# fuzz_sch.net
KiCad netlist of a schematic drawn in EAGLE
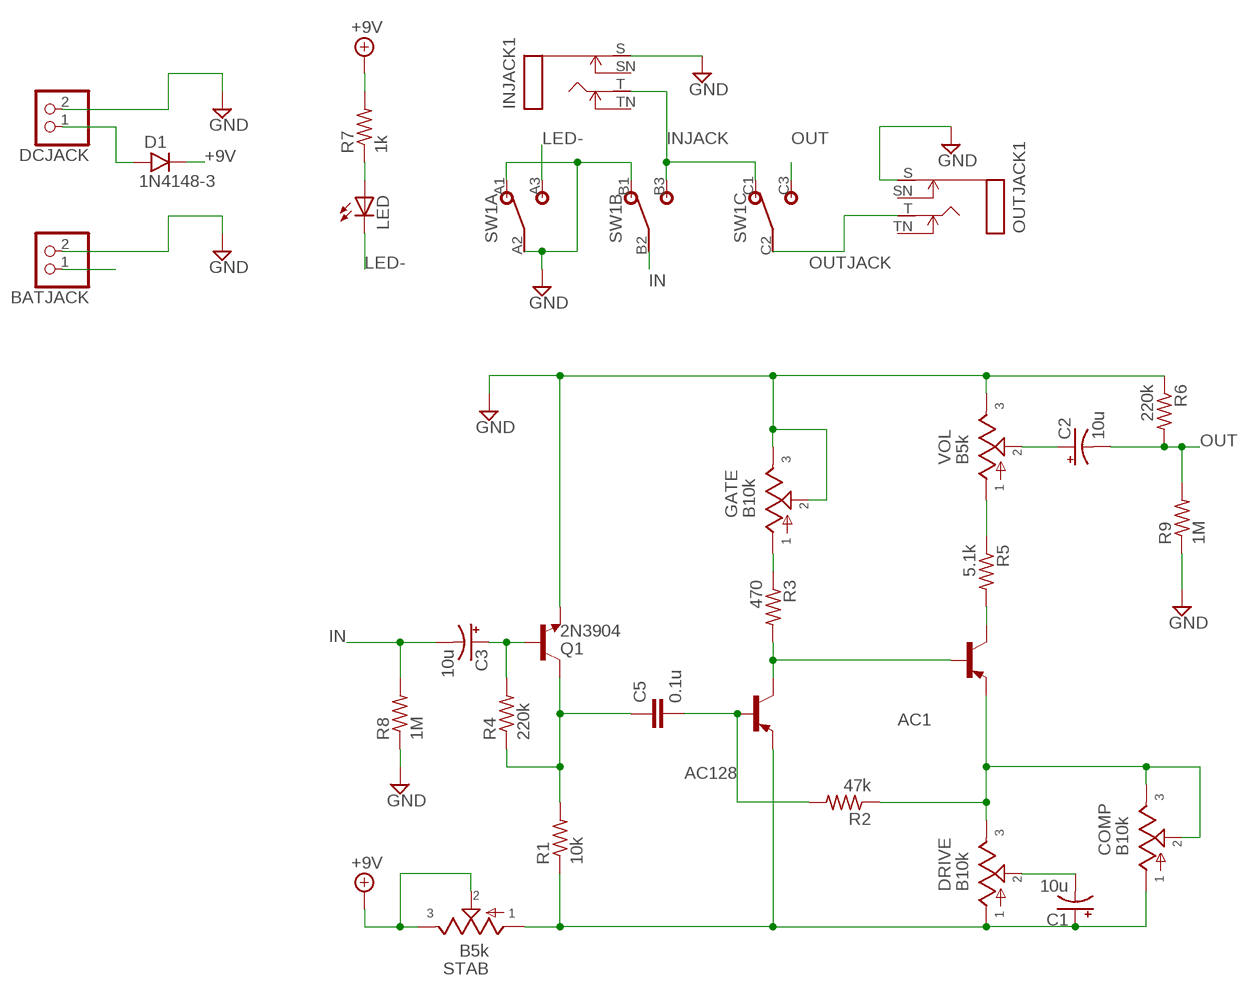
[diagram p0: schematic, sheet 1]

(export (version "E")
  (design (tool "Eeschema 10.0.6"))
  (components
    (comp (ref "AC1")
      (value "-PNP-TO5")
      (footprint "eagle-import:TO5")
      (libsource (lib "eagle-import") (part "-PNP-TO5"))
    )
    (comp (ref "AC128")
      (value "-PNP-TO5")
      (footprint "eagle-import:TO5")
      (libsource (lib "eagle-import") (part "-PNP-TO5"))
    )
    (comp (ref "BATJACK")
      (value "PINHD-1X2")
      (footprint "eagle-import:1X02")
      (libsource (lib "eagle-import") (part "PINHD-1X2"))
    )
    (comp (ref "C1")
      (value "10u")
      (footprint "eagle-import:063_025")
      (libsource (lib "eagle-import") (part "0631"))
    )
    (comp (ref "C2")
      (value "10u")
      (footprint "eagle-import:063_025")
      (libsource (lib "eagle-import") (part "0631"))
    )
    (comp (ref "C3")
      (value "10u")
      (footprint "eagle-import:063_025")
      (libsource (lib "eagle-import") (part "0631"))
    )
    (comp (ref "C5")
      (value "0.1u")
      (footprint "eagle-import:072X035")
      (libsource (lib "eagle-import") (part "072X0352"))
    )
    (comp (ref "COMP")
      (value "B10k")
      (footprint "eagle-import:16MM")
      (libsource (lib "eagle-import") (part "POT16MM"))
    )
    (comp (ref "D1")
      (value "1N4148-3")
      (footprint "eagle-import:DO35-3")
      (libsource (lib "eagle-import") (part "1N4148-3"))
    )
    (comp (ref "DCJACK")
      (value "PINHD-1X2")
      (footprint "eagle-import:1X02")
      (libsource (lib "eagle-import") (part "PINHD-1X2"))
    )
    (comp (ref "DRIVE")
      (value "B10k")
      (footprint "eagle-import:16MM")
      (libsource (lib "eagle-import") (part "POT16MM"))
    )
    (comp (ref "GATE")
      (value "B10k")
      (footprint "eagle-import:16MM")
      (libsource (lib "eagle-import") (part "POT16MM"))
    )
    (comp (ref "INJACK1")
      (value "MONOSWS")
      (footprint "eagle-import:NMJ4HC-S")
      (libsource (lib "eagle-import") (part "MONOSWS"))
    )
    (comp (ref "LED")
      (value "LED5MM")
      (footprint "eagle-import:LED5MM")
      (libsource (lib "eagle-import") (part "LED5MM"))
    )
    (comp (ref "OUTJACK1")
      (value "MONOSWS")
      (footprint "eagle-import:NMJ4HC-S")
      (libsource (lib "eagle-import") (part "MONOSWS"))
    )
    (comp (ref "Q1")
      (value "2N3904")
      (footprint "eagle-import:TO92-")
      (libsource (lib "eagle-import") (part "2N3904"))
    )
    (comp (ref "R1")
      (value "10k")
      (footprint "eagle-import:0207_10")
      (libsource (lib "eagle-import") (part "R-US_0207/10"))
    )
    (comp (ref "R2")
      (value "47k")
      (footprint "eagle-import:0207_10")
      (libsource (lib "eagle-import") (part "R-US_0207/10"))
    )
    (comp (ref "R3")
      (value "470")
      (footprint "eagle-import:0207_10")
      (libsource (lib "eagle-import") (part "R-US_0207/10"))
    )
    (comp (ref "R4")
      (value "220k")
      (footprint "eagle-import:0207_10")
      (libsource (lib "eagle-import") (part "R-US_0207/10"))
    )
    (comp (ref "R5")
      (value "5.1k")
      (footprint "eagle-import:0207_10")
      (libsource (lib "eagle-import") (part "R-US_0207/10"))
    )
    (comp (ref "R6")
      (value "220k")
      (footprint "eagle-import:0207_10")
      (libsource (lib "eagle-import") (part "R-US_0207/10"))
    )
    (comp (ref "R7")
      (value "1k")
      (footprint "eagle-import:0207_10")
      (libsource (lib "eagle-import") (part "R-US_0207/10"))
    )
    (comp (ref "R8")
      (value "1M")
      (footprint "eagle-import:0207_10")
      (libsource (lib "eagle-import") (part "R-US_0207/10"))
    )
    (comp (ref "R9")
      (value "1M")
      (footprint "eagle-import:0207_10")
      (libsource (lib "eagle-import") (part "R-US_0207/10"))
    )
    (comp (ref "STAB")
      (value "B5k")
      (footprint "eagle-import:16MM")
      (libsource (lib "eagle-import") (part "POT16MM"))
    )
    (comp (ref "SW1")
      (value "3PDTBLUE")
      (footprint "eagle-import:CHINABLUE")
      (libsource (lib "eagle-import") (part "3PDTBLUE"))
    )
    (comp (ref "VOL")
      (value "B5k")
      (footprint "eagle-import:16MM")
      (libsource (lib "eagle-import") (part "POT16MM"))
    )
  )
  (nets
    (net (code "1") (name "+9V") (class "Default")
      (node (ref "BATJACK") (pin "1") (pinfunction "1_1") (pintype "passive"))
      (node (ref "D1") (pin "C") (pinfunction "C_C") (pintype "passive"))
      (node (ref "R7") (pin "2") (pinfunction "2_2") (pintype "passive"))
      (node (ref "STAB") (pin "2") (pinfunction "2_2") (pintype "passive"))
      (node (ref "STAB") (pin "3") (pinfunction "3_3") (pintype "passive"))
    )
    (net (code "2") (name "/IN") (class "Default")
      (node (ref "C3") (pin "-") (pinfunction "-_-") (pintype "passive"))
      (node (ref "R8") (pin "2") (pinfunction "2_2") (pintype "passive"))
      (node (ref "SW1") (pin "B2") (pinfunction "2_B2") (pintype "passive"))
    )
    (net (code "3") (name "/INJACK") (class "Default")
      (node (ref "INJACK1") (pin "T") (pinfunction "T_T") (pintype "passive"))
      (node (ref "SW1") (pin "B3") (pinfunction "3_B3") (pintype "passive"))
      (node (ref "SW1") (pin "C1") (pinfunction "1_C1") (pintype "passive"))
    )
    (net (code "4") (name "/LED-") (class "Default")
      (node (ref "LED") (pin "K") (pinfunction "C_K") (pintype "passive"))
      (node (ref "SW1") (pin "A3") (pinfunction "3_A3") (pintype "passive"))
    )
    (net (code "5") (name "/OUT") (class "Default")
      (node (ref "C2") (pin "-") (pinfunction "-_-") (pintype "passive"))
      (node (ref "R6") (pin "2") (pinfunction "2_2") (pintype "passive"))
      (node (ref "R9") (pin "2") (pinfunction "2_2") (pintype "passive"))
      (node (ref "SW1") (pin "C3") (pinfunction "3_C3") (pintype "passive"))
    )
    (net (code "6") (name "/OUTJACK") (class "Default")
      (node (ref "OUTJACK1") (pin "T") (pinfunction "T_T") (pintype "passive"))
      (node (ref "SW1") (pin "C2") (pinfunction "2_C2") (pintype "passive"))
    )
    (net (code "7") (name "GND") (class "Default")
      (node (ref "BATJACK") (pin "2") (pinfunction "2_2") (pintype "passive"))
      (node (ref "DCJACK") (pin "2") (pinfunction "2_2") (pintype "passive"))
      (node (ref "GATE") (pin "2") (pinfunction "2_2") (pintype "passive"))
      (node (ref "GATE") (pin "3") (pinfunction "3_3") (pintype "passive"))
      (node (ref "INJACK1") (pin "S") (pinfunction "S_S") (pintype "passive"))
      (node (ref "OUTJACK1") (pin "S") (pinfunction "S_S") (pintype "passive"))
      (node (ref "Q1") (pin "3") (pinfunction "E_3") (pintype "passive"))
      (node (ref "R6") (pin "1") (pinfunction "1_1") (pintype "passive"))
      (node (ref "R8") (pin "1") (pinfunction "1_1") (pintype "passive"))
      (node (ref "R9") (pin "1") (pinfunction "1_1") (pintype "passive"))
      (node (ref "SW1") (pin "A1") (pinfunction "1_A1") (pintype "passive"))
      (node (ref "SW1") (pin "A2") (pinfunction "2_A2") (pintype "passive"))
      (node (ref "SW1") (pin "B1") (pinfunction "1_B1") (pintype "passive"))
      (node (ref "VOL") (pin "3") (pinfunction "3_3") (pintype "passive"))
    )
    (net (code "8") (name "Net-(AC1-B)") (class "Default")
      (node (ref "AC1") (pin "2") (pinfunction "B_2") (pintype "passive"))
      (node (ref "AC128") (pin "3") (pinfunction "C_3") (pintype "passive"))
      (node (ref "R3") (pin "2") (pinfunction "2_2") (pintype "passive"))
    )
    (net (code "9") (name "Net-(AC1-C)") (class "Default")
      (node (ref "AC1") (pin "3") (pinfunction "C_3") (pintype "passive"))
      (node (ref "R5") (pin "2") (pinfunction "2_2") (pintype "passive"))
    )
    (net (code "10") (name "Net-(AC1-E)") (class "Default")
      (node (ref "AC1") (pin "1") (pinfunction "E_1") (pintype "passive"))
      (node (ref "COMP") (pin "2") (pinfunction "2_2") (pintype "passive"))
      (node (ref "COMP") (pin "3") (pinfunction "3_3") (pintype "passive"))
      (node (ref "DRIVE") (pin "3") (pinfunction "3_3") (pintype "passive"))
      (node (ref "R2") (pin "1") (pinfunction "1_1") (pintype "passive"))
    )
    (net (code "11") (name "Net-(AC128-B)") (class "Default")
      (node (ref "AC128") (pin "2") (pinfunction "B_2") (pintype "passive"))
      (node (ref "C5") (pin "2") (pinfunction "2_2") (pintype "passive"))
      (node (ref "R2") (pin "2") (pinfunction "2_2") (pintype "passive"))
    )
    (net (code "12") (name "Net-(AC128-E)") (class "Default")
      (node (ref "AC128") (pin "1") (pinfunction "E_1") (pintype "passive"))
      (node (ref "C1") (pin "+") (pinfunction "+_+") (pintype "passive"))
      (node (ref "COMP") (pin "1") (pinfunction "1_1") (pintype "passive"))
      (node (ref "DRIVE") (pin "1") (pinfunction "1_1") (pintype "passive"))
      (node (ref "R1") (pin "1") (pinfunction "1_1") (pintype "passive"))
      (node (ref "STAB") (pin "1") (pinfunction "1_1") (pintype "passive"))
    )
    (net (code "13") (name "Net-(C1-Pad-)") (class "Default")
      (node (ref "C1") (pin "-") (pinfunction "-_-") (pintype "passive"))
      (node (ref "DRIVE") (pin "2") (pinfunction "2_2") (pintype "passive"))
    )
    (net (code "14") (name "Net-(C2-Pad+)") (class "Default")
      (node (ref "C2") (pin "+") (pinfunction "+_+") (pintype "passive"))
      (node (ref "VOL") (pin "2") (pinfunction "2_2") (pintype "passive"))
    )
    (net (code "15") (name "Net-(D1-PadA)") (class "Default")
      (node (ref "D1") (pin "A") (pinfunction "A_A") (pintype "passive"))
      (node (ref "DCJACK") (pin "1") (pinfunction "1_1") (pintype "passive"))
    )
    (net (code "16") (name "Net-(GATE-Pad1)") (class "Default")
      (node (ref "GATE") (pin "1") (pinfunction "1_1") (pintype "passive"))
      (node (ref "R3") (pin "1") (pinfunction "1_1") (pintype "passive"))
    )
    (net (code "17") (name "Net-(LED-PadA)") (class "Default")
      (node (ref "LED") (pin "A") (pinfunction "A_A") (pintype "passive"))
      (node (ref "R7") (pin "1") (pinfunction "1_1") (pintype "passive"))
    )
    (net (code "18") (name "Net-(Q1-B)") (class "Default")
      (node (ref "C3") (pin "+") (pinfunction "+_+") (pintype "passive"))
      (node (ref "Q1") (pin "2") (pinfunction "B_2") (pintype "passive"))
      (node (ref "R4") (pin "2") (pinfunction "2_2") (pintype "passive"))
    )
    (net (code "19") (name "Net-(Q1-C)") (class "Default")
      (node (ref "C5") (pin "1") (pinfunction "1_1") (pintype "passive"))
      (node (ref "Q1") (pin "1") (pinfunction "C_1") (pintype "passive"))
      (node (ref "R1") (pin "2") (pinfunction "2_2") (pintype "passive"))
      (node (ref "R4") (pin "1") (pinfunction "1_1") (pintype "passive"))
    )
    (net (code "20") (name "Net-(R5-Pad1)") (class "Default")
      (node (ref "R5") (pin "1") (pinfunction "1_1") (pintype "passive"))
      (node (ref "VOL") (pin "1") (pinfunction "1_1") (pintype "passive"))
    )
    (net (code "21") (name "unconnected-(INJACK1-PadSN)") (class "Default")
      (node (ref "INJACK1") (pin "SN") (pinfunction "SN_SN") (pintype "passive"))
    )
    (net (code "22") (name "unconnected-(INJACK1-PadTN)") (class "Default")
      (node (ref "INJACK1") (pin "TN") (pinfunction "TN_TN") (pintype "passive"))
    )
    (net (code "23") (name "unconnected-(OUTJACK1-PadSN)") (class "Default")
      (node (ref "OUTJACK1") (pin "SN") (pinfunction "SN_SN") (pintype "passive"))
    )
    (net (code "24") (name "unconnected-(OUTJACK1-PadTN)") (class "Default")
      (node (ref "OUTJACK1") (pin "TN") (pinfunction "TN_TN") (pintype "passive"))
    )
  )
)
